# power_supply.net
KiCad netlist of a schematic drawn in Altium Designer
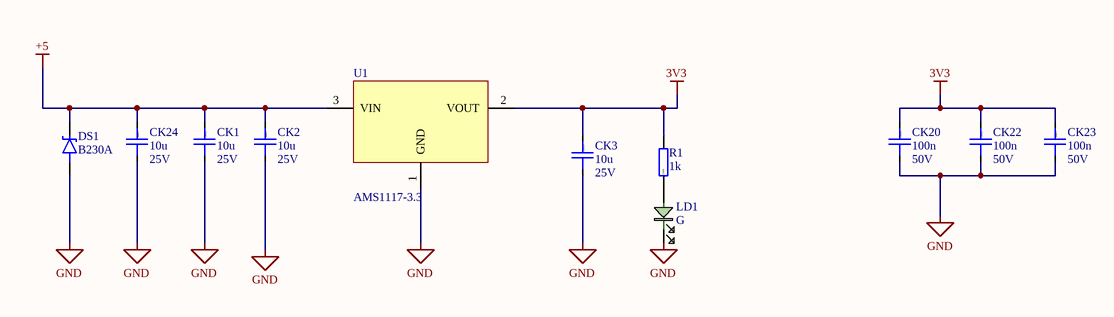
[diagram p0: power_supply.SchDoc]

(export (version "E")
  (design (tool "Eeschema 10.0.6"))
  (components
    (comp (ref "CK1")
      (value "10u")
      (footprint "CAP0805")
      (description "25V 10uF X5R ±10% 0805 Multilayer Ceramic Capacitors MLCC - SMD/SMT ROHS")
      (fields (field (name "JLCPCB PART") "C15850") (field (name "VOLTAGE RATING") "25V"))
      (libsource (lib "Kubikova ultra knihovna") (part "Cap 10u 0805"))
    )
    (comp (ref "CK2")
      (value "10u")
      (footprint "CAP0805")
      (description "25V 10uF X5R ±10% 0805 Multilayer Ceramic Capacitors MLCC - SMD/SMT ROHS")
      (fields (field (name "JLCPCB PART") "C15850") (field (name "VOLTAGE RATING") "25V"))
      (libsource (lib "Kubikova ultra knihovna") (part "Cap 10u 0805"))
    )
    (comp (ref "CK3")
      (value "10u")
      (footprint "CAP0805")
      (description "25V 10uF X5R ±10% 0805 Multilayer Ceramic Capacitors MLCC - SMD/SMT ROHS")
      (fields (field (name "JLCPCB PART") "C15850") (field (name "VOLTAGE RATING") "25V"))
      (libsource (lib "Kubikova ultra knihovna") (part "Cap 10u 0805"))
    )
    (comp (ref "CK20")
      (value "100n")
      (footprint "CAP0603")
      (description "50V 100nF X7R ±10% 0603 Multilayer Ceramic Capacitors MLCC - SMD/SMT ROHS")
      (fields (field (name "JLCPCB PART") "C14663") (field (name "VOLTAGE RATING") "50V"))
      (libsource (lib "Kubikova ultra knihovna") (part "Cap 100n 0603"))
    )
    (comp (ref "CK22")
      (value "100n")
      (footprint "CAP0603")
      (description "50V 100nF X7R ±10% 0603 Multilayer Ceramic Capacitors MLCC - SMD/SMT ROHS")
      (fields (field (name "JLCPCB PART") "C14663") (field (name "VOLTAGE RATING") "50V"))
      (libsource (lib "Kubikova ultra knihovna") (part "Cap 100n 0603"))
    )
    (comp (ref "CK23")
      (value "100n")
      (footprint "CAP0603")
      (description "50V 100nF X7R ±10% 0603 Multilayer Ceramic Capacitors MLCC - SMD/SMT ROHS")
      (fields (field (name "JLCPCB PART") "C14663") (field (name "VOLTAGE RATING") "50V"))
      (libsource (lib "Kubikova ultra knihovna") (part "Cap 100n 0603"))
    )
    (comp (ref "CK24")
      (value "10u")
      (footprint "CAP0805")
      (description "25V 10uF X5R ±10% 0805 Multilayer Ceramic Capacitors MLCC - SMD/SMT ROHS")
      (fields (field (name "JLCPCB PART") "C15850") (field (name "VOLTAGE RATING") "25V"))
      (libsource (lib "Kubikova ultra knihovna") (part "Cap 10u 0805"))
    )
    (comp (ref "DS1")
      (value "B230A")
      (footprint "DIOM4326X23M")
      (description "30V 500mV@2A 2A SMA(DO-214AC) Schottky Diodes ROHS")
      (fields (field (name "JLCPCB PART") "C12889"))
      (libsource (lib "Kubikova ultra knihovna") (part "B230A-13-F"))
    )
    (comp (ref "LD1")
      (value "G")
      (footprint "0603_LED_G")
      (description "0603 Green Led")
      (fields (field (name "JLCPCB PART") "C22371297"))
      (libsource (lib "Kubikova ultra knihovna") (part "LED G 0603"))
    )
    (comp (ref "R1")
      (value "1k")
      (footprint "RESC2012X06N(SMR0805)")
      (description "125mW Thick Film Resistors 150V ±100ppm/℃ ±1% 1kΩ 0805 Chip Resistor - Surface Mount ROHS")
      (fields (field (name "JLCPCB PART") "C17513") (field (name "AUTHOR") "JP/27.03.2014"))
      (libsource (lib "Kubikova ultra knihovna") (part "Res 1k 0805"))
    )
    (comp (ref "U1")
      (value "AMS1117-3.3")
      (footprint "SOT230P700X180-4M")
      (fields (field (name "JLCPCB PART") "C6186"))
      (libsource (lib "Kubikova ultra knihovna") (part "AMS1117-3.3"))
    )
  )
  (nets
    (net (code "1") (name "+5") (class "Default")
      (node (ref "CK1") (pin "1") (pinfunction "1_1") (pintype "passive"))
      (node (ref "CK2") (pin "1") (pinfunction "1_1") (pintype "passive"))
      (node (ref "CK24") (pin "1") (pinfunction "1_1") (pintype "passive"))
      (node (ref "DS1") (pin "1") (pinfunction "1_1") (pintype "passive"))
      (node (ref "U1") (pin "3") (pinfunction "VIN_3") (pintype "power_in"))
    )
    (net (code "2") (name "3V3") (class "Default")
      (node (ref "CK20") (pin "1") (pinfunction "1_1") (pintype "passive"))
      (node (ref "CK22") (pin "1") (pinfunction "1_1") (pintype "passive"))
      (node (ref "CK23") (pin "1") (pinfunction "1_1") (pintype "passive"))
      (node (ref "CK3") (pin "1") (pinfunction "1_1") (pintype "passive"))
      (node (ref "R1") (pin "1") (pinfunction "1_1") (pintype "passive"))
      (node (ref "U1") (pin "2") (pinfunction "VOUT_2") (pintype "power_in"))
    )
    (net (code "3") (name "GND") (class "Default")
      (node (ref "CK1") (pin "2") (pinfunction "2_2") (pintype "passive"))
      (node (ref "CK2") (pin "2") (pinfunction "2_2") (pintype "passive"))
      (node (ref "CK20") (pin "2") (pinfunction "2_2") (pintype "passive"))
      (node (ref "CK22") (pin "2") (pinfunction "2_2") (pintype "passive"))
      (node (ref "CK23") (pin "2") (pinfunction "2_2") (pintype "passive"))
      (node (ref "CK24") (pin "2") (pinfunction "2_2") (pintype "passive"))
      (node (ref "CK3") (pin "2") (pinfunction "2_2") (pintype "passive"))
      (node (ref "DS1") (pin "2") (pinfunction "2_2") (pintype "passive"))
      (node (ref "LD1") (pin "2") (pintype "passive"))
      (node (ref "U1") (pin "1") (pinfunction "GND_1") (pintype "power_in"))
    )
    (net (code "4") (name "Net-(LD1-Pad1)") (class "Default")
      (node (ref "LD1") (pin "1") (pintype "passive"))
      (node (ref "R1") (pin "2") (pinfunction "2_2") (pintype "passive"))
    )
  )
)
